# STM.net
KiCad netlist of a schematic drawn in Altium Designer
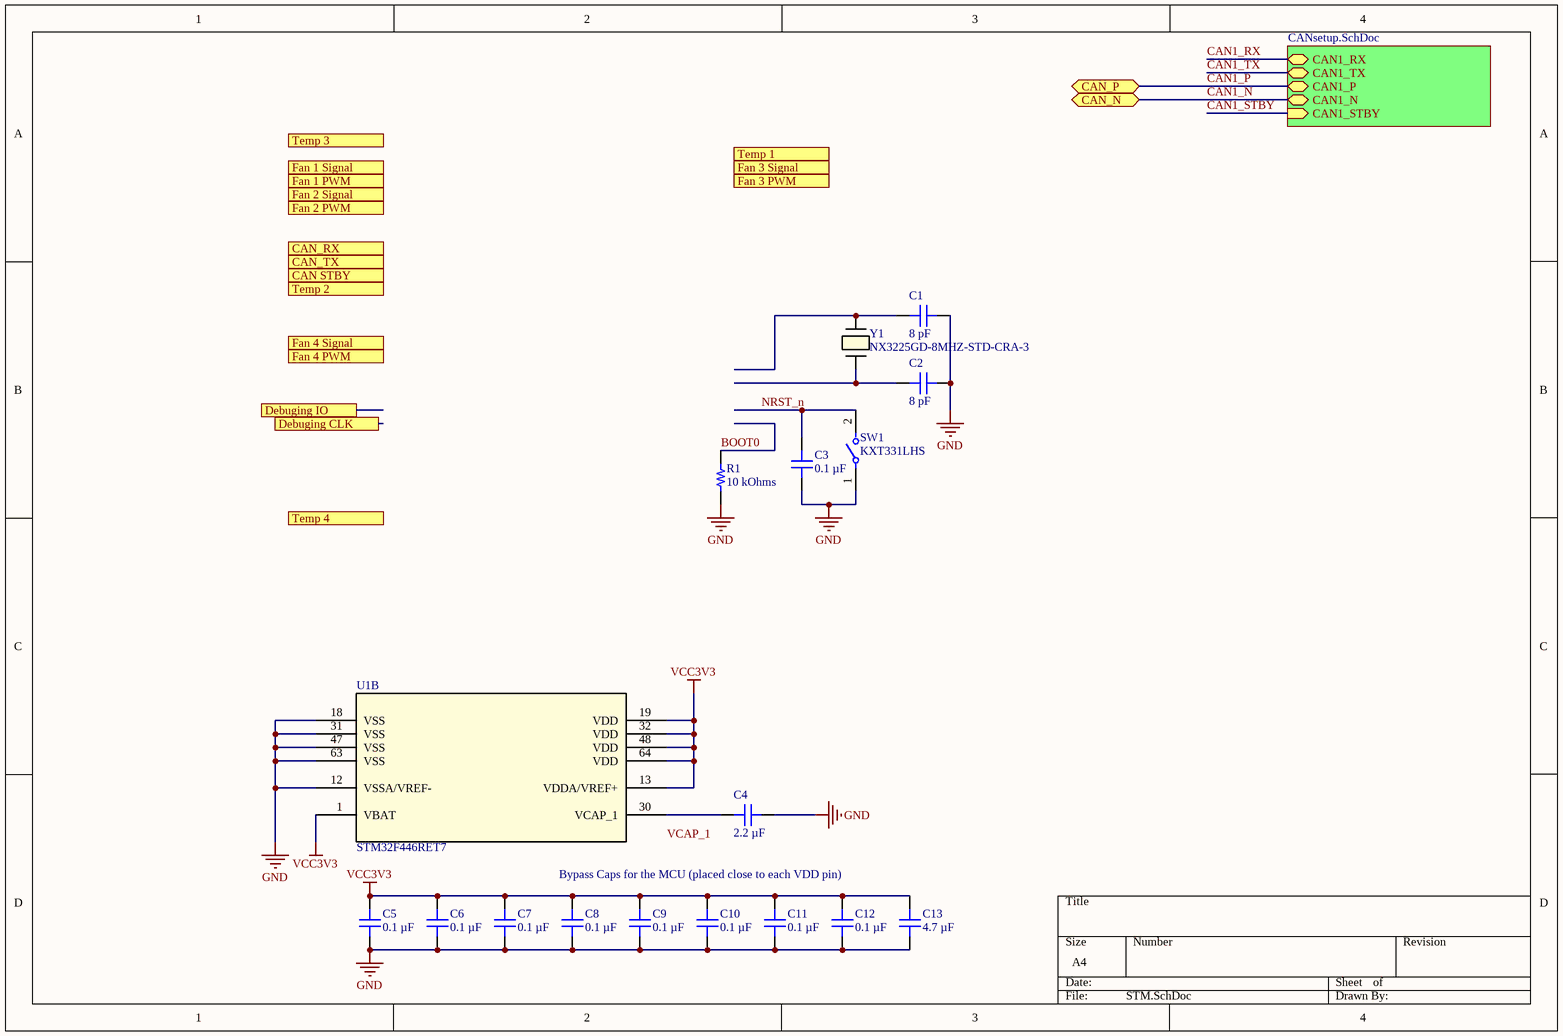
[diagram p0: STM.SchDoc]

(export (version "E")
  (design (tool "Eeschema 10.0.6"))
  (components
    (comp (ref "C1")
      (value "8 pF")
      (footprint "CAP 0402_1005")
      (description "CAP CER 8PF 50V C0G/NP0 0402")
      (fields
        (field (name "PART NUMBER") "GCM1555C1H8R0FA16D")
        (field (name "MANUFACTURER") "Murata Electronics")
      )
      (libsource (lib "Celestial Altium Library - altium_library") (part "Capacitor"))
    )
    (comp (ref "C2")
      (value "8 pF")
      (footprint "CAP 0402_1005")
      (description "CAP CER 8PF 50V C0G/NP0 0402")
      (fields
        (field (name "PART NUMBER") "GCM1555C1H8R0FA16D")
        (field (name "MANUFACTURER") "Murata Electronics")
      )
      (libsource (lib "Celestial Altium Library - altium_library") (part "Capacitor"))
    )
    (comp (ref "C3")
      (value "0.1 µF")
      (footprint "CAP 01005_0402")
      (description "CAP CER 0.1UF 6.3V X5R 01005")
      (fields
        (field (name "PART NUMBER") "CL02A104KQ2NNNC")
        (field (name "MANUFACTURER") "Samsung Electro-Mechanics")
      )
      (libsource (lib "Celestial Altium Library - altium_library") (part "Capacitor"))
    )
    (comp (ref "C4")
      (value "2.2 µF")
      (footprint "CAP 0402_1005")
      (description "CAP CER 2.2UF 16V X5R 0402")
      (fields
        (field (name "PART NUMBER") "CL05A225KO5NQNC")
        (field (name "MANUFACTURER") "Samsung Electro-Mechanics")
      )
      (libsource (lib "Celestial Altium Library - altium_library") (part "Capacitor"))
    )
    (comp (ref "C5")
      (value "0.1 µF")
      (footprint "CAP 01005_0402")
      (description "CAP CER 0.1UF 6.3V X5R 01005")
      (fields
        (field (name "PART NUMBER") "CL02A104KQ2NNNC")
        (field (name "MANUFACTURER") "Samsung Electro-Mechanics")
      )
      (libsource (lib "Celestial Altium Library - altium_library") (part "Capacitor"))
    )
    (comp (ref "C6")
      (value "0.1 µF")
      (footprint "CAP 01005_0402")
      (description "CAP CER 0.1UF 6.3V X5R 01005")
      (fields
        (field (name "PART NUMBER") "CL02A104KQ2NNNC")
        (field (name "MANUFACTURER") "Samsung Electro-Mechanics")
      )
      (libsource (lib "Celestial Altium Library - altium_library") (part "Capacitor"))
    )
    (comp (ref "C7")
      (value "0.1 µF")
      (footprint "CAP 01005_0402")
      (description "CAP CER 0.1UF 6.3V X5R 01005")
      (fields
        (field (name "PART NUMBER") "CL02A104KQ2NNNC")
        (field (name "MANUFACTURER") "Samsung Electro-Mechanics")
      )
      (libsource (lib "Celestial Altium Library - altium_library") (part "Capacitor"))
    )
    (comp (ref "C8")
      (value "0.1 µF")
      (footprint "CAP 01005_0402")
      (description "CAP CER 0.1UF 6.3V X5R 01005")
      (fields
        (field (name "PART NUMBER") "CL02A104KQ2NNNC")
        (field (name "MANUFACTURER") "Samsung Electro-Mechanics")
      )
      (libsource (lib "Celestial Altium Library - altium_library") (part "Capacitor"))
    )
    (comp (ref "C9")
      (value "0.1 µF")
      (footprint "CAP 01005_0402")
      (description "CAP CER 0.1UF 6.3V X5R 01005")
      (fields
        (field (name "PART NUMBER") "CL02A104KQ2NNNC")
        (field (name "MANUFACTURER") "Samsung Electro-Mechanics")
      )
      (libsource (lib "Celestial Altium Library - altium_library") (part "Capacitor"))
    )
    (comp (ref "C10")
      (value "0.1 µF")
      (footprint "CAP 01005_0402")
      (description "CAP CER 0.1UF 6.3V X5R 01005")
      (fields
        (field (name "PART NUMBER") "CL02A104KQ2NNNC")
        (field (name "MANUFACTURER") "Samsung Electro-Mechanics")
      )
      (libsource (lib "Celestial Altium Library - altium_library") (part "Capacitor"))
    )
    (comp (ref "C11")
      (value "0.1 µF")
      (footprint "CAP 01005_0402")
      (description "CAP CER 0.1UF 6.3V X5R 01005")
      (fields
        (field (name "PART NUMBER") "CL02A104KQ2NNNC")
        (field (name "MANUFACTURER") "Samsung Electro-Mechanics")
      )
      (libsource (lib "Celestial Altium Library - altium_library") (part "Capacitor"))
    )
    (comp (ref "C12")
      (value "0.1 µF")
      (footprint "CAP 01005_0402")
      (description "CAP CER 0.1UF 6.3V X5R 01005")
      (fields
        (field (name "PART NUMBER") "CL02A104KQ2NNNC")
        (field (name "MANUFACTURER") "Samsung Electro-Mechanics")
      )
      (libsource (lib "Celestial Altium Library - altium_library") (part "Capacitor"))
    )
    (comp (ref "C13")
      (value "4.7 µF")
      (footprint "CAP 0402_1005")
      (description "CAP CER 4.7UF 16V X5R 0402")
      (fields
        (field (name "PART NUMBER") "CL05A475MO5NUNC")
        (field (name "MANUFACTURER") "Samsung Electro-Mechanics")
      )
      (libsource (lib "Celestial Altium Library - altium_library") (part "Capacitor"))
    )
    (comp (ref "R1")
      (value "10 kOhms")
      (footprint "RES 0201_0603")
      (description "RES SMD 10K OHM 1% 1/20W 0201")
      (fields (field (name "PART NUMBER") "CRCW020110K0FKED") (field (name "MANUFACTURER") "Vishay Dale"))
      (libsource (lib "Celestial Altium Library - altium_library") (part "Resistor"))
    )
    (comp (ref "SW1")
      (value "KXT331LHS")
      (footprint "FP-KXT331LHS-MFG")
      (description "SWITCH TACTILE SPST-NO 0.02A 15V")
      (libsource (lib "Altium Content Vault") (part "bb27bde45df87f1f469753f287ef5ae"))
    )
    (comp (ref "U1")
      (value "STM32F446RET7")
      (footprint "LQFP64-10x10mm")
      (description "No Description Available")
      (fields (field (name "COPYRIGHT") "Copyright (C) 2024 Ultra Librarian. All rights reserved."))
      (libsource (lib "STM32F446RET7") (part "STM32F446RET7"))
    )
    (comp (ref "Y1")
      (value "NX3225GD-8MHZ-STD-CRA-3")
      (footprint "XTAL_NX3225GD-8MHZ-STD-CRA-3_NDK")
      (description "No Description Available")
      (fields (field (name "COPYRIGHT") "Copyright (C) 2024 Ultra Librarian. All rights reserved."))
      (libsource (lib "NX3225GD-8MHZ-STD-CRA-3") (part "NX3225GD-8MHZ-STD-CRA-3"))
    )
  )
  (nets
    (net (code "1") (name "/BOOT0") (class "Default")
      (node (ref "R1") (pin "2") (pinfunction "2_2") (pintype "passive"))
    )
    (net (code "20") (name "/NRST_n") (class "Default")
      (node (ref "C3") (pin "1") (pinfunction "1_1") (pintype "passive"))
      (node (ref "SW1") (pin "2") (pinfunction "2_2") (pintype "passive"))
    )
    (net (code "26") (name "GND") (class "Default")
      (node (ref "C1") (pin "1") (pinfunction "1_1") (pintype "passive"))
      (node (ref "C10") (pin "2") (pinfunction "2_2") (pintype "passive"))
      (node (ref "C11") (pin "2") (pinfunction "2_2") (pintype "passive"))
      (node (ref "C12") (pin "2") (pinfunction "2_2") (pintype "passive"))
      (node (ref "C13") (pin "1") (pinfunction "1_1") (pintype "passive"))
      (node (ref "C2") (pin "1") (pinfunction "1_1") (pintype "passive"))
      (node (ref "C3") (pin "2") (pinfunction "2_2") (pintype "passive"))
      (node (ref "C4") (pin "1") (pinfunction "1_1") (pintype "passive"))
      (node (ref "C5") (pin "2") (pinfunction "2_2") (pintype "passive"))
      (node (ref "C6") (pin "2") (pinfunction "2_2") (pintype "passive"))
      (node (ref "C7") (pin "2") (pinfunction "2_2") (pintype "passive"))
      (node (ref "C8") (pin "2") (pinfunction "2_2") (pintype "passive"))
      (node (ref "C9") (pin "2") (pinfunction "2_2") (pintype "passive"))
      (node (ref "R1") (pin "1") (pinfunction "1_1") (pintype "passive"))
      (node (ref "SW1") (pin "1") (pinfunction "1_1") (pintype "passive"))
      (node (ref "U1") (pin "12") (pinfunction "VSSA/VREF-_12") (pintype "power_in"))
      (node (ref "U1") (pin "18") (pinfunction "VSS_18") (pintype "power_in"))
      (node (ref "U1") (pin "31") (pinfunction "VSS_31") (pintype "power_in"))
      (node (ref "U1") (pin "47") (pinfunction "VSS_47") (pintype "power_in"))
      (node (ref "U1") (pin "63") (pinfunction "VSS_63") (pintype "power_in"))
    )
    (net (code "27") (name "Net-(C1-Pad2)") (class "Default")
      (node (ref "C1") (pin "2") (pinfunction "2_2") (pintype "passive"))
      (node (ref "Y1") (pin "1") (pinfunction "1_1") (pintype "passive"))
    )
    (net (code "28") (name "Net-(C2-Pad2)") (class "Default")
      (node (ref "C2") (pin "2") (pinfunction "2_2") (pintype "passive"))
      (node (ref "Y1") (pin "2") (pinfunction "2_2") (pintype "passive"))
    )
    (net (code "29") (name "Net-(U1B-VCAP_1)") (class "Default")
      (node (ref "C4") (pin "2") (pinfunction "2_2") (pintype "passive"))
      (node (ref "U1") (pin "30") (pinfunction "VCAP_1_30") (pintype "power_in"))
    )
    (net (code "30") (name "VCC3V3") (class "Default")
      (node (ref "C10") (pin "1") (pinfunction "1_1") (pintype "passive"))
      (node (ref "C11") (pin "1") (pinfunction "1_1") (pintype "passive"))
      (node (ref "C12") (pin "1") (pinfunction "1_1") (pintype "passive"))
      (node (ref "C13") (pin "2") (pinfunction "2_2") (pintype "passive"))
      (node (ref "C5") (pin "1") (pinfunction "1_1") (pintype "passive"))
      (node (ref "C6") (pin "1") (pinfunction "1_1") (pintype "passive"))
      (node (ref "C7") (pin "1") (pinfunction "1_1") (pintype "passive"))
      (node (ref "C8") (pin "1") (pinfunction "1_1") (pintype "passive"))
      (node (ref "C9") (pin "1") (pinfunction "1_1") (pintype "passive"))
      (node (ref "U1") (pin "1") (pinfunction "VBAT_1") (pintype "power_in"))
      (node (ref "U1") (pin "13") (pinfunction "VDDA/VREF+_13") (pintype "power_in"))
      (node (ref "U1") (pin "19") (pinfunction "VDD_19") (pintype "power_in"))
      (node (ref "U1") (pin "32") (pinfunction "VDD_32") (pintype "power_in"))
      (node (ref "U1") (pin "48") (pinfunction "VDD_48") (pintype "power_in"))
      (node (ref "U1") (pin "64") (pinfunction "VDD_64") (pintype "power_in"))
    )
  )
)
